# design.net
KiCad netlist of a schematic drawn in Altium Designer
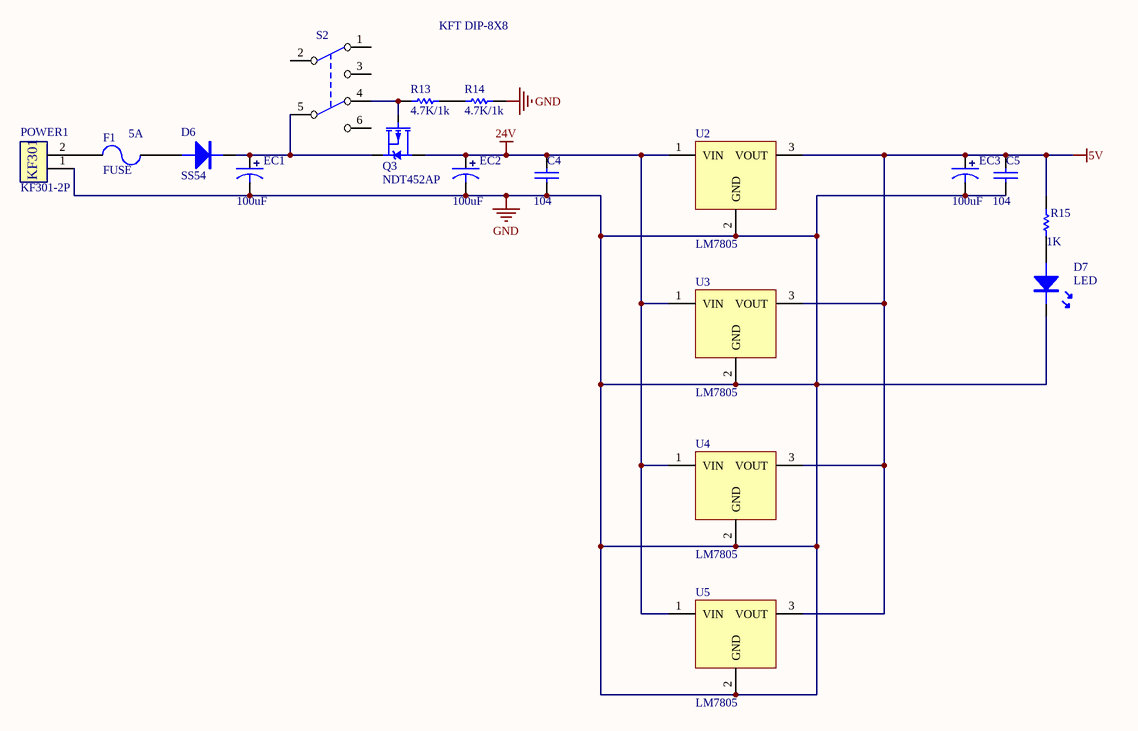
[diagram p0: 电源模块.SchDoc]

(export (version "E")
  (design (tool "Eeschema 10.0.6"))
  (components
    (comp (ref "C4")
      (value "104")
      (footprint "0603C")
      (description "无极性电容")
      (fields (field (name "Comment") "CAP"))
      (libsource (lib "电容") (part "CAP"))
    )
    (comp (ref "C5")
      (value "104")
      (footprint "0603C")
      (description "无极性电容")
      (fields (field (name "Comment") "CAP"))
      (libsource (lib "电容") (part "CAP"))
    )
    (comp (ref "D6")
      (value "SS54")
      (footprint "SMA/DO-214AC")
      (description "普通二极管")
      (libsource (lib "二极管") (part "DIODE"))
    )
    (comp (ref "D7") (value "LED") (footprint "LED3-YEL") (libsource (lib "LED") (part "LED")))
    (comp (ref "EC1")
      (value "100uF")
      (footprint "DIP-EC6.3X11")
      (description "电解电容")
      (fields (field (name "Comment") "SMD_ECAP"))
      (libsource (lib "电容") (part "SMD_ECAP"))
    )
    (comp (ref "EC2")
      (value "100uF")
      (footprint "DIP-EC6.3X11")
      (description "电解电容")
      (fields (field (name "Comment") "SMD_ECAP"))
      (libsource (lib "电容") (part "SMD_ECAP"))
    )
    (comp (ref "EC3")
      (value "100uF")
      (footprint "DIP-EC6.3X11")
      (description "贴片电解电容")
      (fields (field (name "Comment") "SMD_ECAP"))
      (libsource (lib "电容") (part "SMD_ECAP"))
    )
    (comp (ref "F1")
      (value "FUSE")
      (footprint "FUSE-RAD0.2")
      (fields (field (name "ALTIUM_VALUE") "5A"))
      (libsource (lib "保险丝") (part "FUSE"))
    )
    (comp (ref "POWER1")
      (value "KF301-2P")
      (footprint "KF301-5.0-2P")
      (libsource (lib "KF301") (part "KF301-2P"))
    )
    (comp (ref "Q3")
      (value "NDT452AP")
      (footprint "SOT223")
      (description "P沟道场效应管")
      (libsource (lib "MOS管") (part "P-MOS"))
    )
    (comp (ref "R13")
      (value "4.7K/1k")
      (footprint "0603R")
      (fields (field (name "Comment") "RES"))
      (libsource (lib "电阻") (part "RES"))
    )
    (comp (ref "R14")
      (value "4.7K/1k")
      (footprint "0603R")
      (fields (field (name "Comment") "RES"))
      (libsource (lib "电阻") (part "RES"))
    )
    (comp (ref "R15")
      (value "1K")
      (footprint "0603R")
      (fields (field (name "Comment") "RES"))
      (libsource (lib "电阻") (part "RES"))
    )
    (comp (ref "S2")
      (value "KFT DIP-8X8")
      (footprint "KFT DIP-8X8")
      (libsource (lib "电源开关") (part "KFT DIP-8X8"))
    )
    (comp (ref "U2") (value "LM7805") (footprint "TO220A") (libsource (lib "电源芯片") (part "LM7805")))
    (comp (ref "U3") (value "LM7805") (footprint "TO220A") (libsource (lib "电源芯片") (part "LM7805")))
    (comp (ref "U4") (value "LM7805") (footprint "TO220A") (libsource (lib "电源芯片") (part "LM7805")))
    (comp (ref "U5") (value "LM7805") (footprint "TO220A") (libsource (lib "电源芯片") (part "LM7805")))
  )
  (nets
    (net (code "1") (name "5V") (class "Default")
      (node (ref "C5") (pin "2") (pinfunction "2_2") (pintype "passive"))
      (node (ref "EC3") (pin "1") (pinfunction "1_1") (pintype "passive"))
      (node (ref "R15") (pin "2") (pinfunction "2_2") (pintype "passive"))
      (node (ref "U2") (pin "3") (pinfunction "VOUT_3") (pintype "passive"))
      (node (ref "U3") (pin "3") (pinfunction "VOUT_3") (pintype "passive"))
      (node (ref "U4") (pin "3") (pinfunction "VOUT_3") (pintype "passive"))
      (node (ref "U5") (pin "3") (pinfunction "VOUT_3") (pintype "passive"))
    )
    (net (code "2") (name "24V") (class "Default")
      (node (ref "C4") (pin "2") (pinfunction "2_2") (pintype "passive"))
      (node (ref "EC2") (pin "1") (pinfunction "1_1") (pintype "passive"))
      (node (ref "Q3") (pin "2") (pinfunction "D_2") (pintype "passive"))
      (node (ref "U2") (pin "1") (pinfunction "VIN_1") (pintype "passive"))
      (node (ref "U3") (pin "1") (pinfunction "VIN_1") (pintype "passive"))
      (node (ref "U4") (pin "1") (pinfunction "VIN_1") (pintype "passive"))
      (node (ref "U5") (pin "1") (pinfunction "VIN_1") (pintype "passive"))
    )
    (net (code "3") (name "GND") (class "Default")
      (node (ref "C4") (pin "1") (pinfunction "1_1") (pintype "passive"))
      (node (ref "C5") (pin "1") (pinfunction "1_1") (pintype "passive"))
      (node (ref "D7") (pin "K") (pinfunction "K_K") (pintype "passive"))
      (node (ref "EC1") (pin "2") (pinfunction "2_2") (pintype "passive"))
      (node (ref "EC2") (pin "2") (pinfunction "2_2") (pintype "passive"))
      (node (ref "EC3") (pin "2") (pinfunction "2_2") (pintype "passive"))
      (node (ref "POWER1") (pin "1") (pinfunction "1_1") (pintype "passive"))
      (node (ref "R14") (pin "2") (pinfunction "2_2") (pintype "passive"))
      (node (ref "U2") (pin "2") (pinfunction "GND_2") (pintype "passive"))
      (node (ref "U3") (pin "2") (pinfunction "GND_2") (pintype "passive"))
      (node (ref "U4") (pin "2") (pinfunction "GND_2") (pintype "passive"))
      (node (ref "U5") (pin "2") (pinfunction "GND_2") (pintype "passive"))
    )
    (net (code "4") (name "Net-(D6-PadA)") (class "Default")
      (node (ref "D6") (pin "A") (pinfunction "A_A") (pintype "passive"))
      (node (ref "F1") (pin "2") (pinfunction "2_2") (pintype "passive"))
    )
    (net (code "5") (name "Net-(D7-PadA)") (class "Default")
      (node (ref "D7") (pin "A") (pinfunction "A_A") (pintype "passive"))
      (node (ref "R15") (pin "1") (pinfunction "1_1") (pintype "passive"))
    )
    (net (code "6") (name "Net-(F1-Pad1)") (class "Default")
      (node (ref "F1") (pin "1") (pinfunction "1_1") (pintype "passive"))
      (node (ref "POWER1") (pin "2") (pinfunction "2_2") (pintype "passive"))
    )
    (net (code "7") (name "Net-(Q3-G)") (class "Default")
      (node (ref "Q3") (pin "1") (pinfunction "G_1") (pintype "passive"))
      (node (ref "R13") (pin "1") (pinfunction "1_1") (pintype "passive"))
      (node (ref "S2") (pin "4") (pinfunction "4_4") (pintype "passive"))
    )
    (net (code "8") (name "Net-(Q3-S)") (class "Default")
      (node (ref "D6") (pin "K") (pinfunction "K_K") (pintype "passive"))
      (node (ref "EC1") (pin "1") (pinfunction "1_1") (pintype "passive"))
      (node (ref "Q3") (pin "3") (pinfunction "S_3") (pintype "passive"))
      (node (ref "S2") (pin "5") (pinfunction "5_5") (pintype "passive"))
    )
    (net (code "9") (name "Net-(R13-Pad2)") (class "Default")
      (node (ref "R13") (pin "2") (pinfunction "2_2") (pintype "passive"))
      (node (ref "R14") (pin "1") (pinfunction "1_1") (pintype "passive"))
    )
    (net (code "10") (name "unconnected-(S2-Pad1)") (class "Default")
      (node (ref "S2") (pin "1") (pinfunction "1_1") (pintype "passive"))
    )
    (net (code "11") (name "unconnected-(S2-Pad2)") (class "Default")
      (node (ref "S2") (pin "2") (pinfunction "2_2") (pintype "passive"))
    )
    (net (code "12") (name "unconnected-(S2-Pad3)") (class "Default")
      (node (ref "S2") (pin "3") (pinfunction "3_3") (pintype "passive"))
    )
    (net (code "13") (name "unconnected-(S2-Pad6)") (class "Default")
      (node (ref "S2") (pin "6") (pinfunction "6_6") (pintype "passive"))
    )
  )
)
